# CATS-EUROC-Pyro_Enable.net
KiCad netlist of a schematic drawn in Altium Designer
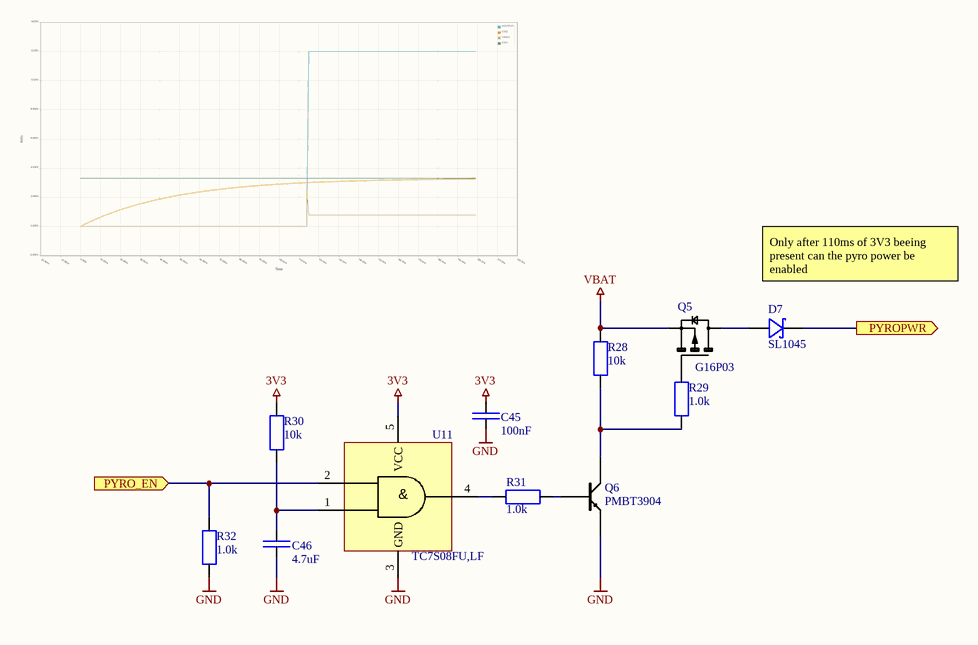
[diagram p0: CATS-EUROC-Pyro_Enable.SchDoc]

(export (version "E")
  (design (tool "Eeschema 10.0.6"))
  (components
    (comp (ref "C45")
      (value "100nF")
      (footprint "SMD Keramikkondensator 0402")
      (description "SMD Ceramic Capacitor E6")
      (libsource (lib "CATS-EUROC") (part "E6 - 100nF"))
    )
    (comp (ref "C46")
      (value "4.7uF")
      (footprint "SMD Keramikkondensator 0402")
      (description "SMD Ceramic Capacitor E6")
      (libsource (lib "CATS-EUROC") (part "E6 - 4.7uF"))
    )
    (comp (ref "D7")
      (value "SL1045")
      (footprint "SMD Diode TO-277")
      (description "45V 470mV@10A 10A TO-277 Schottky Barrier Diodes")
      (libsource (lib "Diodes") (part "SL1045"))
    )
    (comp (ref "Q5")
      (value "G16P03")
      (footprint "SMD MOSFET DFN 3x3 EP")
      (description "30V 16A 35W")
      (libsource (lib "Electronic Switches") (part "G16P03"))
    )
    (comp (ref "Q6")
      (value "PMBT3904")
      (footprint "SMD Transistor SOT-23")
      (description "40 V, 200 mA NPN switching transisto")
      (libsource (lib "Electronic Switches") (part "PMBT3904"))
    )
    (comp (ref "R28")
      (value "10k")
      (footprint "SMD Widerstand 0402")
      (description "SMD Chip Resistor E24")
      (libsource (lib "CATS-EUROC") (part "E24 - 10k"))
    )
    (comp (ref "R29")
      (value "1.0k")
      (footprint "SMD Widerstand 0402")
      (description "SMD Chip Resistor E24")
      (libsource (lib "CATS-EUROC") (part "E24 - 1.0k"))
    )
    (comp (ref "R30")
      (value "10k")
      (footprint "SMD Widerstand 0402")
      (description "SMD Chip Resistor E24")
      (libsource (lib "CATS-EUROC") (part "E24 - 10k"))
    )
    (comp (ref "R31")
      (value "1.0k")
      (footprint "SMD Widerstand 0402")
      (description "SMD Chip Resistor E24")
      (libsource (lib "") (part "E24 - 1.0k_1"))
    )
    (comp (ref "R32")
      (value "1.0k")
      (footprint "SMD Widerstand 0402")
      (description "SMD Chip Resistor E24")
      (libsource (lib "CATS-EUROC") (part "E24 - 1.0k"))
    )
    (comp (ref "U11")
      (value "TC7S08FU,LF")
      (footprint "SMD IC SSOP5-P-0.65A (SOT353-1)")
      (description "AND Gate SSOP5-P-0.65A")
      (libsource (lib "Digital") (part "TC7S08FU,LF"))
    )
  )
  (nets
    (net (code "1") (name "/PYROPWR") (class "Default")
      (node (ref "D7") (pin "K") (pinfunction "K_K") (pintype "passive"))
    )
    (net (code "2") (name "/PYRO_EN") (class "Default")
      (node (ref "R32") (pin "2") (pinfunction "2_2") (pintype "passive"))
      (node (ref "U11") (pin "2") (pinfunction "IN_2") (pintype "passive"))
    )
    (net (code "3") (name "3V3") (class "Default")
      (node (ref "C45") (pin "2") (pinfunction "2_2") (pintype "passive"))
      (node (ref "R30") (pin "2") (pinfunction "2_2") (pintype "passive"))
      (node (ref "U11") (pin "5") (pinfunction "VCC_5") (pintype "passive"))
    )
    (net (code "4") (name "GND") (class "Default")
      (node (ref "C45") (pin "1") (pinfunction "1_1") (pintype "passive"))
      (node (ref "C46") (pin "1") (pinfunction "1_1") (pintype "passive"))
      (node (ref "Q6") (pin "E") (pintype "passive"))
      (node (ref "R32") (pin "1") (pinfunction "1_1") (pintype "passive"))
      (node (ref "U11") (pin "3") (pinfunction "GND_3") (pintype "passive"))
    )
    (net (code "5") (name "Net-(C46-Pad2)") (class "Default")
      (node (ref "C46") (pin "2") (pinfunction "2_2") (pintype "passive"))
      (node (ref "R30") (pin "1") (pinfunction "1_1") (pintype "passive"))
      (node (ref "U11") (pin "1") (pinfunction "IN_1") (pintype "passive"))
    )
    (net (code "6") (name "Net-(D7-PadA)") (class "Default")
      (node (ref "D7") (pin "A") (pinfunction "A_A") (pintype "passive"))
      (node (ref "Q5") (pin "D") (pinfunction "D_D") (pintype "passive"))
    )
    (net (code "7") (name "Net-(Q5-PadG)") (class "Default")
      (node (ref "Q5") (pin "G") (pinfunction "G_G") (pintype "passive"))
      (node (ref "R29") (pin "2") (pinfunction "2_2") (pintype "passive"))
    )
    (net (code "8") (name "Net-(Q6-PadB)") (class "Default")
      (node (ref "Q6") (pin "B") (pintype "passive"))
      (node (ref "R31") (pin "1") (pinfunction "1_1") (pintype "passive"))
    )
    (net (code "9") (name "Net-(Q6-PadC)") (class "Default")
      (node (ref "Q6") (pin "C") (pintype "passive"))
      (node (ref "R28") (pin "1") (pinfunction "1_1") (pintype "passive"))
      (node (ref "R29") (pin "1") (pinfunction "1_1") (pintype "passive"))
    )
    (net (code "10") (name "Net-(U11-OUT)") (class "Default")
      (node (ref "R31") (pin "2") (pinfunction "2_2") (pintype "passive"))
      (node (ref "U11") (pin "4") (pinfunction "OUT_4") (pintype "passive"))
    )
    (net (code "11") (name "VBAT") (class "Default")
      (node (ref "Q5") (pin "S") (pinfunction "S_S") (pintype "passive"))
      (node (ref "R28") (pin "2") (pinfunction "2_2") (pintype "passive"))
    )
  )
)
